# Log_and_Anti-Log.net
KiCad netlist of a schematic drawn in Altium Designer
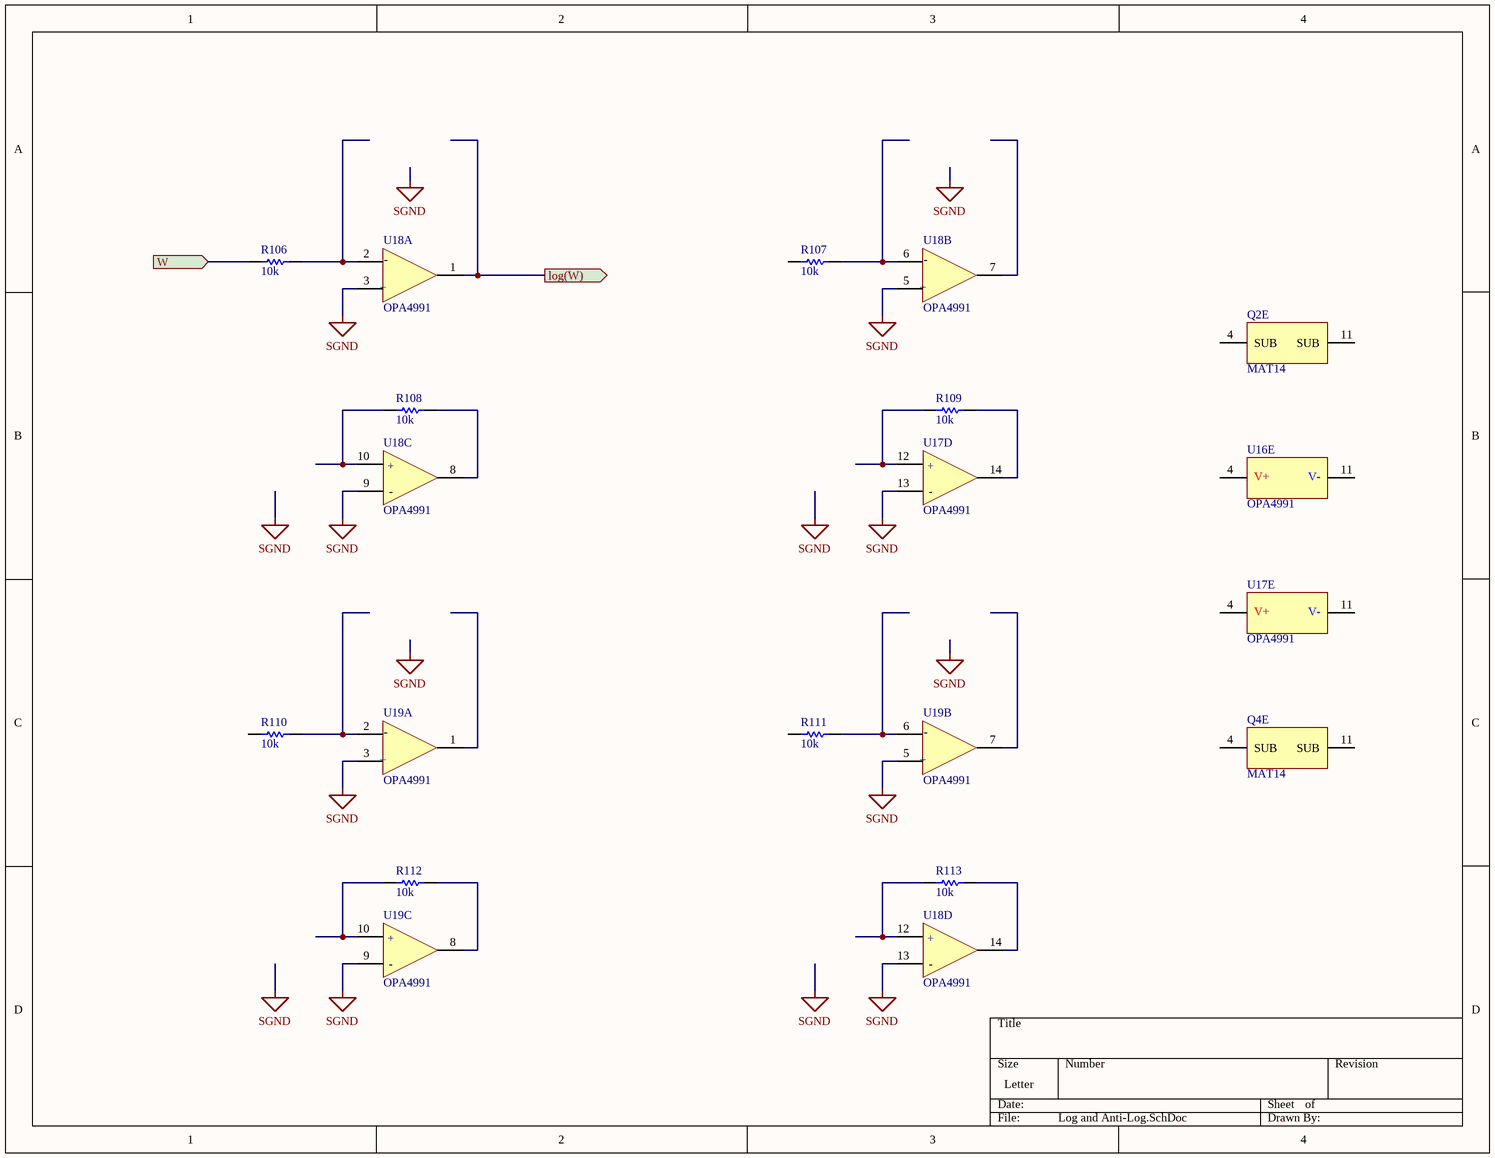
[diagram p0: Log and Anti-Log.SchDoc]

(export (version "E")
  (design (tool "Eeschema 10.0.6"))
  (components
    (comp (ref "Q2")
      (value "MAT14")
      (footprint "FP-R-14-IPC_B")
      (description "TRANS 4NPN 40V 0.03A 14SO")
      (libsource (lib "DRC") (part "MAT14ARZ"))
    )
    (comp (ref "Q4")
      (value "MAT14")
      (footprint "FP-R-14-IPC_B")
      (description "TRANS 4NPN 40V 0.03A 14SO")
      (libsource (lib "DRC") (part "MAT14ARZ"))
    )
    (comp (ref "R106")
      (value "10k")
      (description "Resistor")
      (libsource (lib "Simulation Generic Components") (part "Resistor"))
    )
    (comp (ref "R107")
      (value "10k")
      (description "Resistor")
      (libsource (lib "Simulation Generic Components") (part "Resistor"))
    )
    (comp (ref "R108")
      (value "10k")
      (description "Resistor")
      (libsource (lib "Simulation Generic Components") (part "Resistor"))
    )
    (comp (ref "R109")
      (value "10k")
      (description "Resistor")
      (libsource (lib "Simulation Generic Components") (part "Resistor"))
    )
    (comp (ref "R110")
      (value "10k")
      (description "Resistor")
      (libsource (lib "Simulation Generic Components") (part "Resistor"))
    )
    (comp (ref "R111")
      (value "10k")
      (description "Resistor")
      (libsource (lib "Simulation Generic Components") (part "Resistor"))
    )
    (comp (ref "R112")
      (value "10k")
      (description "Resistor")
      (libsource (lib "Simulation Generic Components") (part "Resistor"))
    )
    (comp (ref "R113")
      (value "10k")
      (description "Resistor")
      (libsource (lib "Simulation Generic Components") (part "Resistor"))
    )
    (comp (ref "U16")
      (value "OPA4991")
      (footprint "FP-D0014A-IPC_B")
      (description "40-V, DUAL 4.5MHZ, RAIL-TO-RAIL")
      (libsource (lib "DRC") (part "OPA4991IDR"))
    )
    (comp (ref "U17")
      (value "OPA4991")
      (footprint "FP-D0014A-IPC_B")
      (description "40-V, DUAL 4.5MHZ, RAIL-TO-RAIL")
      (libsource (lib "DRC") (part "OPA4991IDR"))
    )
    (comp (ref "U18")
      (value "OPA4991")
      (footprint "FP-D0014A-IPC_B")
      (description "40-V, DUAL 4.5MHZ, RAIL-TO-RAIL")
      (libsource (lib "") (part "OPA4991IDR_1"))
    )
    (comp (ref "U19")
      (value "OPA4991")
      (footprint "FP-D0014A-IPC_B")
      (description "40-V, DUAL 4.5MHZ, RAIL-TO-RAIL")
      (libsource (lib "") (part "OPA4991IDR_1"))
    )
  )
  (nets
    (net (code "1") (name "/W") (class "Default")
      (node (ref "R106") (pin "1") (pinfunction "1_1") (pintype "passive"))
    )
    (net (code "2") (name "/log(W)") (class "Default")
      (node (ref "U18") (pin "1") (pinfunction "OUT1_1") (pintype "passive"))
    )
    (net (code "3") (name "Net-(U17D-IN4+)") (class "Default")
      (node (ref "R109") (pin "1") (pinfunction "1_1") (pintype "passive"))
      (node (ref "U17") (pin "12") (pinfunction "IN4+_12") (pintype "tri_state"))
    )
    (net (code "4") (name "Net-(U17D-OUT4)") (class "Default")
      (node (ref "R109") (pin "2") (pinfunction "2_2") (pintype "passive"))
      (node (ref "U17") (pin "14") (pinfunction "OUT4_14") (pintype "passive"))
    )
    (net (code "5") (name "Net-(U18A-IN1-)") (class "Default")
      (node (ref "R106") (pin "2") (pinfunction "2_2") (pintype "passive"))
      (node (ref "U18") (pin "2") (pinfunction "IN1-_2") (pintype "tri_state"))
    )
    (net (code "6") (name "Net-(U18B-IN2-)") (class "Default")
      (node (ref "R107") (pin "2") (pinfunction "2_2") (pintype "passive"))
      (node (ref "U18") (pin "6") (pinfunction "IN2-_6") (pintype "tri_state"))
    )
    (net (code "7") (name "Net-(U18C-IN3+)") (class "Default")
      (node (ref "R108") (pin "1") (pinfunction "1_1") (pintype "passive"))
      (node (ref "U18") (pin "10") (pinfunction "IN3+_10") (pintype "tri_state"))
    )
    (net (code "8") (name "Net-(U18C-OUT3)") (class "Default")
      (node (ref "R108") (pin "2") (pinfunction "2_2") (pintype "passive"))
      (node (ref "U18") (pin "8") (pinfunction "OUT3_8") (pintype "passive"))
    )
    (net (code "9") (name "Net-(U18D-IN4+)") (class "Default")
      (node (ref "R113") (pin "1") (pinfunction "1_1") (pintype "passive"))
      (node (ref "U18") (pin "12") (pinfunction "IN4+_12") (pintype "tri_state"))
    )
    (net (code "10") (name "Net-(U18D-OUT4)") (class "Default")
      (node (ref "R113") (pin "2") (pinfunction "2_2") (pintype "passive"))
      (node (ref "U18") (pin "14") (pinfunction "OUT4_14") (pintype "passive"))
    )
    (net (code "11") (name "Net-(U19A-IN1-)") (class "Default")
      (node (ref "R110") (pin "2") (pinfunction "2_2") (pintype "passive"))
      (node (ref "U19") (pin "2") (pinfunction "IN1-_2") (pintype "tri_state"))
    )
    (net (code "12") (name "Net-(U19B-IN2-)") (class "Default")
      (node (ref "R111") (pin "2") (pinfunction "2_2") (pintype "passive"))
      (node (ref "U19") (pin "6") (pinfunction "IN2-_6") (pintype "tri_state"))
    )
    (net (code "13") (name "Net-(U19C-IN3+)") (class "Default")
      (node (ref "R112") (pin "1") (pinfunction "1_1") (pintype "passive"))
      (node (ref "U19") (pin "10") (pinfunction "IN3+_10") (pintype "tri_state"))
    )
    (net (code "14") (name "Net-(U19C-OUT3)") (class "Default")
      (node (ref "R112") (pin "2") (pinfunction "2_2") (pintype "passive"))
      (node (ref "U19") (pin "8") (pinfunction "OUT3_8") (pintype "passive"))
    )
    (net (code "15") (name "SGND") (class "Default")
      (node (ref "U17") (pin "13") (pinfunction "IN4-_13") (pintype "tri_state"))
      (node (ref "U18") (pin "13") (pinfunction "IN4-_13") (pintype "tri_state"))
      (node (ref "U18") (pin "3") (pinfunction "IN1+_3") (pintype "tri_state"))
      (node (ref "U18") (pin "5") (pinfunction "IN2+_5") (pintype "tri_state"))
      (node (ref "U18") (pin "9") (pinfunction "IN3-_9") (pintype "tri_state"))
      (node (ref "U19") (pin "3") (pinfunction "IN1+_3") (pintype "tri_state"))
      (node (ref "U19") (pin "5") (pinfunction "IN2+_5") (pintype "tri_state"))
      (node (ref "U19") (pin "9") (pinfunction "IN3-_9") (pintype "tri_state"))
    )
    (net (code "16") (name "unconnected-(Q2E-SUB-Pad4)") (class "Default")
      (node (ref "Q2") (pin "4") (pinfunction "SUB_4") (pintype "passive"))
    )
    (net (code "17") (name "unconnected-(Q2E-SUB-Pad11)") (class "Default")
      (node (ref "Q2") (pin "11") (pinfunction "SUB_11") (pintype "passive"))
    )
    (net (code "18") (name "unconnected-(Q4E-SUB-Pad4)") (class "Default")
      (node (ref "Q4") (pin "4") (pinfunction "SUB_4") (pintype "passive"))
    )
    (net (code "19") (name "unconnected-(Q4E-SUB-Pad11)") (class "Default")
      (node (ref "Q4") (pin "11") (pinfunction "SUB_11") (pintype "passive"))
    )
    (net (code "20") (name "unconnected-(R107-Pad1)") (class "Default")
      (node (ref "R107") (pin "1") (pinfunction "1_1") (pintype "passive"))
    )
    (net (code "21") (name "unconnected-(R110-Pad1)") (class "Default")
      (node (ref "R110") (pin "1") (pinfunction "1_1") (pintype "passive"))
    )
    (net (code "22") (name "unconnected-(R111-Pad1)") (class "Default")
      (node (ref "R111") (pin "1") (pinfunction "1_1") (pintype "passive"))
    )
    (net (code "23") (name "unconnected-(U16E-V+-Pad4)") (class "Default")
      (node (ref "U16") (pin "4") (pinfunction "V+_4") (pintype "power_in"))
    )
    (net (code "24") (name "unconnected-(U16E-V--Pad11)") (class "Default")
      (node (ref "U16") (pin "11") (pinfunction "V-_11") (pintype "power_in"))
    )
    (net (code "25") (name "unconnected-(U17E-V+-Pad4)") (class "Default")
      (node (ref "U17") (pin "4") (pinfunction "V+_4") (pintype "power_in"))
    )
    (net (code "26") (name "unconnected-(U17E-V--Pad11)") (class "Default")
      (node (ref "U17") (pin "11") (pinfunction "V-_11") (pintype "power_in"))
    )
    (net (code "27") (name "unconnected-(U18B-OUT2-Pad7)") (class "Default")
      (node (ref "U18") (pin "7") (pinfunction "OUT2_7") (pintype "passive"))
    )
    (net (code "28") (name "unconnected-(U19A-OUT1-Pad1)") (class "Default")
      (node (ref "U19") (pin "1") (pinfunction "OUT1_1") (pintype "passive"))
    )
    (net (code "29") (name "unconnected-(U19B-OUT2-Pad7)") (class "Default")
      (node (ref "U19") (pin "7") (pinfunction "OUT2_7") (pintype "passive"))
    )
  )
)
